# Bee_Hive_MainBoard.net
KiCad netlist of a schematic drawn in Altium Designer
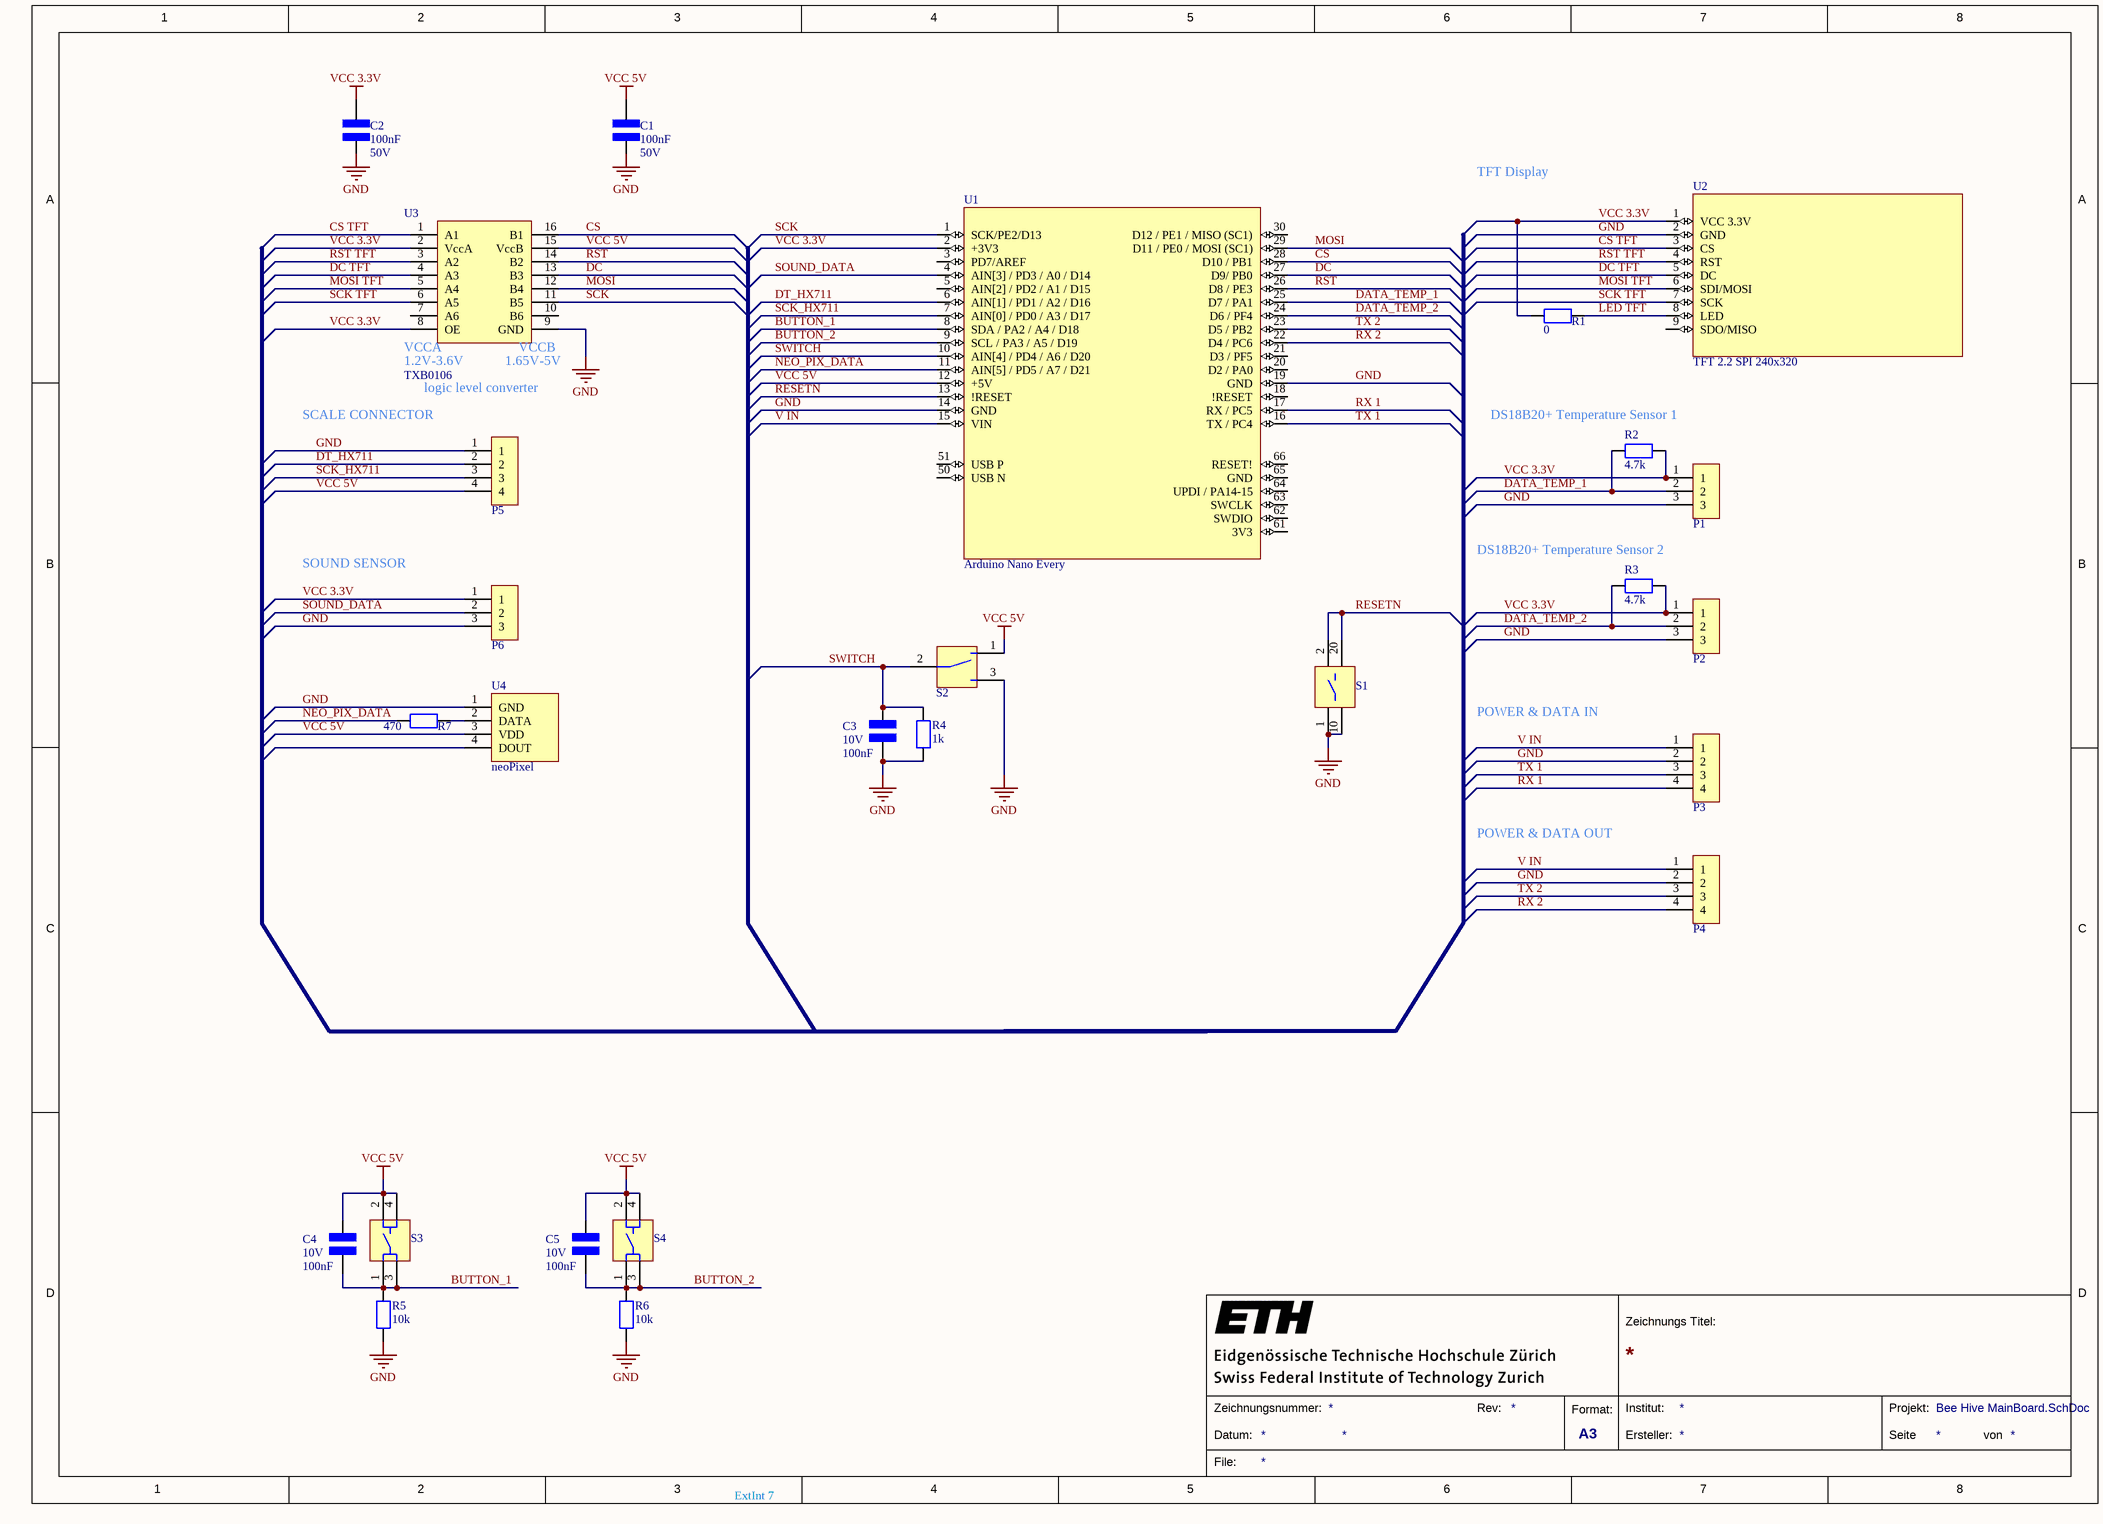
[diagram p0: Bee Hive MainBoard.SchDoc]

(export (version "E")
  (design (tool "Eeschema 10.0.6"))
  (components
    (comp (ref "C1")
      (value "100nF")
      (footprint "CAP 0603")
      (description "C CERAMIC SMD")
      (fields (field (name "UMAX") "50V") (field (name "Comment") "100nF 0603_1"))
      (libsource (lib "Library CAP") (part "100nF 0603_1"))
    )
    (comp (ref "C2")
      (value "100nF")
      (footprint "CAP 0603")
      (description "C CERAMIC SMD")
      (fields (field (name "UMAX") "50V") (field (name "Comment") "100nF 0603_1"))
      (libsource (lib "Library CAP") (part "100nF 0603_1"))
    )
    (comp (ref "C3")
      (value "100nF")
      (footprint "CAP 0603")
      (description "C CERAMIC SMD")
      (fields (field (name "UMAX") "10V") (field (name "Comment") "100nF 0603"))
      (libsource (lib "Library CAP") (part "100nF 0603"))
    )
    (comp (ref "C4")
      (value "100nF")
      (footprint "CAP 0603")
      (description "C CERAMIC SMD")
      (fields (field (name "UMAX") "10V") (field (name "Comment") "100nF 0603"))
      (libsource (lib "Library CAP") (part "100nF 0603"))
    )
    (comp (ref "C5")
      (value "100nF")
      (footprint "CAP 0603")
      (description "C CERAMIC SMD")
      (fields (field (name "UMAX") "10V") (field (name "Comment") "100nF 0603"))
      (libsource (lib "Library CAP") (part "100nF 0603"))
    )
    (comp (ref "P1")
      (value "3-Pin Right Angle Housing")
      (footprint "3PIN - RND 205-EK254-2.54-03P")
      (description "3-Pin")
      (libsource (lib "Library Scematic") (part "3-Pin Screw Terminal"))
    )
    (comp (ref "P2")
      (value "3-Pin Right Angle Housing")
      (footprint "3PIN - RND 205-EK254-2.54-03P")
      (description "3-Pin")
      (libsource (lib "Library Scematic") (part "3-Pin Screw Terminal"))
    )
    (comp (ref "P3")
      (value "4-Pin Right Angle Housing")
      (footprint "4PIN - RND 205-EK254-2.54-04P")
      (description "4-Pin")
      (libsource (lib "Library Scematic") (part "4-Pin Screw Terminal"))
    )
    (comp (ref "P4")
      (value "4-Pin Right Angle Housing")
      (footprint "4PIN - RND 205-EK254-2.54-04P")
      (description "4-Pin")
      (libsource (lib "Library Scematic") (part "4-Pin Screw Terminal"))
    )
    (comp (ref "P5")
      (value "4-Pin Right Angle Housing")
      (footprint "4PIN - RND 205-EK254-2.54-04P")
      (description "4-Pin")
      (libsource (lib "Library Scematic") (part "4-Pin Screw Terminal"))
    )
    (comp (ref "P6")
      (value "3-Pin Right Angle Housing")
      (footprint "3PIN - RND 205-EK254-2.54-03P")
      (description "3-Pin")
      (libsource (lib "Library Scematic") (part "3-Pin Screw Terminal"))
    )
    (comp (ref "R1")
      (value "0")
      (footprint "RES 0603 FOOTPRINT")
      (description "R SMD")
      (fields (field (name "Comment") "0 Ohm 0603"))
      (libsource (lib "Library RES") (part "0 Ohm 0603"))
    )
    (comp (ref "R2")
      (value "4.7k")
      (footprint "RES 0603 FOOTPRINT")
      (description "R SMD")
      (fields (field (name "Comment") "4.7k Ohm 0603"))
      (libsource (lib "Library RES") (part "4.7k Ohm 0603"))
    )
    (comp (ref "R3")
      (value "4.7k")
      (footprint "RES 0603 FOOTPRINT")
      (description "R SMD")
      (fields (field (name "Comment") "4.7k Ohm 0603"))
      (libsource (lib "Library RES") (part "4.7k Ohm 0603"))
    )
    (comp (ref "R4")
      (value "1k")
      (footprint "RES 0603 FOOTPRINT")
      (description "R SMD")
      (fields (field (name "Comment") "1k Ohm 0603"))
      (libsource (lib "Library RES") (part "1k Ohm 0603"))
    )
    (comp (ref "R5")
      (value "10k")
      (footprint "RES 0603 FOOTPRINT")
      (description "R SMD")
      (fields (field (name "Comment") "10k Ohm 0603"))
      (libsource (lib "Library RES") (part "10k Ohm 0603"))
    )
    (comp (ref "R6")
      (value "10k")
      (footprint "RES 0603 FOOTPRINT")
      (description "R SMD")
      (fields (field (name "Comment") "10k Ohm 0603"))
      (libsource (lib "Library RES") (part "10k Ohm 0603"))
    )
    (comp (ref "R7")
      (value "470")
      (footprint "RES 0603 FOOTPRINT")
      (description "R SMD")
      (fields (field (name "Comment") "470 Ohm 0603"))
      (libsource (lib "Library RES") (part "470 Ohm 0603"))
    )
    (comp (ref "S1")
      (value "Taster Print_SMD_2")
      (footprint "Taster Print - SMD - KMR241G LFS")
      (description "Taster")
      (libsource (lib "Library Scematic") (part "Taster Print_SMD_2"))
    )
    (comp (ref "S2")
      (value "Schiebeschalter 7A11-A1PCAE2")
      (footprint "schiebeschalter 7A11-A1PCAE2")
      (libsource (lib "Library Scematic") (part "Schiebeschalter 7A11-A1PCAE2"))
    )
    (comp (ref "S3")
      (value "Taster Print_SMD_3")
      (footprint "Taster Print RND 210-00212")
      (description "Taster")
      (libsource (lib "Library Scematic") (part "Taster Print_SMD_5"))
    )
    (comp (ref "S4")
      (value "Taster Print_SMD_3")
      (footprint "Taster Print RND 210-00212")
      (description "Taster")
      (libsource (lib "Library Scematic") (part "Taster Print_SMD_5"))
    )
    (comp (ref "U1")
      (value "Arduino Nano Every")
      (footprint "Arduino Nano Every")
      (description "https://store.arduino.cc/nano-every-pack")
      (libsource (lib "Library Scematic") (part "Arduino Nano Every"))
    )
    (comp (ref "U2")
      (value "TFT 2.2 SPI 240x320")
      (footprint "TFT 2.2 SPI 240x320")
      (libsource (lib "Library Scematic") (part "TFT 2.2 SPI 240x320"))
    )
    (comp (ref "U3")
      (value "TXB0106")
      (footprint "TSSOP-16L")
      (description "Level Converter TXB0106")
      (libsource (lib "Library Scematic") (part "TXB0106 Level Converter"))
    )
    (comp (ref "U4")
      (value "neoPixel")
      (footprint "neoPixel 5050 adafruit 1655")
      (description "neoPixel 5050 adafruit 1655")
      (libsource (lib "Library Scematic") (part "neoPixel 5050 adafruit 1655"))
    )
  )
  (nets
    (net (code "1") (name "/BUTTON_1") (class "Default")
      (node (ref "C4") (pin "2") (pinfunction "2_2") (pintype "passive"))
      (node (ref "R5") (pin "2") (pinfunction "2_2") (pintype "passive"))
      (node (ref "S3") (pin "1") (pinfunction "1_1") (pintype "passive"))
      (node (ref "S3") (pin "3") (pinfunction "3_3") (pintype "passive"))
      (node (ref "U1") (pin "8") (pinfunction "SDA_/_PA2_/_A4_/_D18_8") (pintype "bidirectional"))
    )
    (net (code "2") (name "/BUTTON_2") (class "Default")
      (node (ref "C5") (pin "2") (pinfunction "2_2") (pintype "passive"))
      (node (ref "R6") (pin "2") (pinfunction "2_2") (pintype "passive"))
      (node (ref "S4") (pin "1") (pinfunction "1_1") (pintype "passive"))
      (node (ref "S4") (pin "3") (pinfunction "3_3") (pintype "passive"))
      (node (ref "U1") (pin "9") (pinfunction "SCL_/_PA3_/_A5_/_D19_9") (pintype "bidirectional"))
    )
    (net (code "3") (name "/CS") (class "Default")
      (node (ref "U1") (pin "28") (pinfunction "D10_/_PB1_28") (pintype "bidirectional"))
      (node (ref "U3") (pin "16") (pinfunction "B1_16") (pintype "passive"))
    )
    (net (code "4") (name "/CS TFT") (class "Default")
      (node (ref "U2") (pin "3") (pinfunction "CS_3") (pintype "bidirectional"))
      (node (ref "U3") (pin "1") (pinfunction "A1_1") (pintype "power_in"))
    )
    (net (code "5") (name "/DATA_TEMP_1") (class "Default")
      (node (ref "P1") (pin "2") (pinfunction "2_2") (pintype "passive"))
      (node (ref "R2") (pin "2") (pinfunction "2_2") (pintype "passive"))
      (node (ref "U1") (pin "25") (pinfunction "D7_/_PA1_25") (pintype "bidirectional"))
    )
    (net (code "6") (name "/DATA_TEMP_2") (class "Default")
      (node (ref "P2") (pin "2") (pinfunction "2_2") (pintype "passive"))
      (node (ref "R3") (pin "2") (pinfunction "2_2") (pintype "passive"))
      (node (ref "U1") (pin "24") (pinfunction "D6_/_PF4_24") (pintype "bidirectional"))
    )
    (net (code "7") (name "/DC") (class "Default")
      (node (ref "U1") (pin "27") (pinfunction "D9/_PB0_27") (pintype "bidirectional"))
      (node (ref "U3") (pin "13") (pinfunction "B3_13") (pintype "passive"))
    )
    (net (code "8") (name "/DC TFT") (class "Default")
      (node (ref "U2") (pin "5") (pinfunction "DC_5") (pintype "bidirectional"))
      (node (ref "U3") (pin "4") (pinfunction "A3_4") (pintype "passive"))
    )
    (net (code "9") (name "/DT_HX711") (class "Default")
      (node (ref "P5") (pin "2") (pinfunction "2_2") (pintype "passive"))
      (node (ref "U1") (pin "6") (pinfunction "AIN[1]_/_PD1_/_A2_/_D16_6") (pintype "bidirectional"))
    )
    (net (code "10") (name "/LED TFT") (class "Default")
      (node (ref "R1") (pin "1") (pinfunction "1_1") (pintype "passive"))
      (node (ref "U2") (pin "8") (pinfunction "LED_8") (pintype "bidirectional"))
    )
    (net (code "11") (name "/MOSI") (class "Default")
      (node (ref "U1") (pin "29") (pinfunction "D11_/_PE0_/_MOSI_(SC1)_29") (pintype "bidirectional"))
      (node (ref "U3") (pin "12") (pinfunction "B4_12") (pintype "passive"))
    )
    (net (code "12") (name "/MOSI TFT") (class "Default")
      (node (ref "U2") (pin "6") (pinfunction "SDI/MOSI_6") (pintype "bidirectional"))
      (node (ref "U3") (pin "5") (pinfunction "A4_5") (pintype "passive"))
    )
    (net (code "13") (name "/NEO_PIX_DATA") (class "Default")
      (node (ref "R7") (pin "1") (pinfunction "1_1") (pintype "passive"))
      (node (ref "U1") (pin "11") (pinfunction "AIN[5]_/_PD5_/_A7_/_D21_11") (pintype "bidirectional"))
    )
    (net (code "14") (name "/RESETN") (class "Default")
      (node (ref "S1") (pin "2") (pinfunction "2_2") (pintype "passive"))
      (node (ref "S1") (pin "20") (pinfunction "20_20") (pintype "passive"))
      (node (ref "U1") (pin "13") (pinfunction "!RESET_13") (pintype "bidirectional"))
    )
    (net (code "15") (name "/RST") (class "Default")
      (node (ref "U1") (pin "26") (pinfunction "D8_/_PE3_26") (pintype "bidirectional"))
      (node (ref "U3") (pin "14") (pinfunction "B2_14") (pintype "passive"))
    )
    (net (code "16") (name "/RST TFT") (class "Default")
      (node (ref "U2") (pin "4") (pinfunction "RST_4") (pintype "bidirectional"))
      (node (ref "U3") (pin "3") (pinfunction "A2_3") (pintype "passive"))
    )
    (net (code "17") (name "/RX 1") (class "Default")
      (node (ref "P3") (pin "4") (pinfunction "4_4") (pintype "passive"))
      (node (ref "U1") (pin "17") (pinfunction "RX_/_PC5_17") (pintype "bidirectional"))
    )
    (net (code "18") (name "/RX 2") (class "Default")
      (node (ref "P4") (pin "4") (pinfunction "4_4") (pintype "passive"))
      (node (ref "U1") (pin "22") (pinfunction "D4_/_PC6_22") (pintype "bidirectional"))
    )
    (net (code "19") (name "/SCK") (class "Default")
      (node (ref "U1") (pin "1") (pinfunction "SCK/PE2/D13_1") (pintype "bidirectional"))
      (node (ref "U3") (pin "11") (pinfunction "B5_11") (pintype "passive"))
    )
    (net (code "20") (name "/SCK TFT") (class "Default")
      (node (ref "U2") (pin "7") (pinfunction "SCK_7") (pintype "bidirectional"))
      (node (ref "U3") (pin "6") (pinfunction "A5_6") (pintype "passive"))
    )
    (net (code "21") (name "/SCK_HX711") (class "Default")
      (node (ref "P5") (pin "3") (pinfunction "3_3") (pintype "passive"))
      (node (ref "U1") (pin "7") (pinfunction "AIN[0]_/_PD0_/_A3_/_D17_7") (pintype "bidirectional"))
    )
    (net (code "22") (name "/SOUND_DATA") (class "Default")
      (node (ref "P6") (pin "2") (pinfunction "2_2") (pintype "passive"))
      (node (ref "U1") (pin "4") (pinfunction "AIN[3]_/_PD3_/_A0_/_D14_4") (pintype "bidirectional"))
    )
    (net (code "23") (name "/SWITCH") (class "Default")
      (node (ref "C3") (pin "1") (pinfunction "1_1") (pintype "passive"))
      (node (ref "R4") (pin "2") (pinfunction "2_2") (pintype "passive"))
      (node (ref "S2") (pin "2") (pinfunction "2_2") (pintype "passive"))
      (node (ref "U1") (pin "10") (pinfunction "AIN[4]_/_PD4_/_A6_/_D20_10") (pintype "bidirectional"))
    )
    (net (code "24") (name "/TX 1") (class "Default")
      (node (ref "P3") (pin "3") (pinfunction "3_3") (pintype "passive"))
      (node (ref "U1") (pin "16") (pinfunction "TX_/_PC4_16") (pintype "bidirectional"))
    )
    (net (code "25") (name "/TX 2") (class "Default")
      (node (ref "P4") (pin "3") (pinfunction "3_3") (pintype "passive"))
      (node (ref "U1") (pin "23") (pinfunction "D5_/_PB2_23") (pintype "bidirectional"))
    )
    (net (code "26") (name "/V IN") (class "Default")
      (node (ref "P3") (pin "1") (pinfunction "1_1") (pintype "passive"))
      (node (ref "P4") (pin "1") (pinfunction "1_1") (pintype "passive"))
      (node (ref "U1") (pin "15") (pinfunction "VIN_15") (pintype "bidirectional"))
    )
    (net (code "27") (name "GND") (class "Default")
      (node (ref "C1") (pin "1") (pinfunction "1_1") (pintype "passive"))
      (node (ref "C2") (pin "1") (pinfunction "1_1") (pintype "passive"))
      (node (ref "C3") (pin "2") (pinfunction "2_2") (pintype "passive"))
      (node (ref "P1") (pin "3") (pinfunction "3_3") (pintype "passive"))
      (node (ref "P2") (pin "3") (pinfunction "3_3") (pintype "passive"))
      (node (ref "P3") (pin "2") (pinfunction "2_2") (pintype "passive"))
      (node (ref "P4") (pin "2") (pinfunction "2_2") (pintype "passive"))
      (node (ref "P5") (pin "1") (pinfunction "1_1") (pintype "passive"))
      (node (ref "P6") (pin "3") (pinfunction "3_3") (pintype "passive"))
      (node (ref "R4") (pin "1") (pinfunction "1_1") (pintype "passive"))
      (node (ref "R5") (pin "1") (pinfunction "1_1") (pintype "passive"))
      (node (ref "R6") (pin "1") (pinfunction "1_1") (pintype "passive"))
      (node (ref "S1") (pin "1") (pinfunction "1_1") (pintype "passive"))
      (node (ref "S1") (pin "10") (pinfunction "10_10") (pintype "passive"))
      (node (ref "S2") (pin "3") (pinfunction "3_3") (pintype "passive"))
      (node (ref "U1") (pin "14") (pinfunction "GND_14") (pintype "bidirectional"))
      (node (ref "U1") (pin "19") (pinfunction "GND_19") (pintype "bidirectional"))
      (node (ref "U2") (pin "2") (pinfunction "GND_2") (pintype "bidirectional"))
      (node (ref "U3") (pin "9") (pinfunction "GND_9") (pintype "passive"))
      (node (ref "U4") (pin "1") (pinfunction "GND_1") (pintype "passive"))
    )
    (net (code "28") (name "Net-(U4-DATA)") (class "Default")
      (node (ref "R7") (pin "2") (pinfunction "2_2") (pintype "passive"))
      (node (ref "U4") (pin "2") (pinfunction "DATA_2") (pintype "passive"))
    )
    (net (code "29") (name "VCC 3.3V") (class "Default")
      (node (ref "C2") (pin "2") (pinfunction "2_2") (pintype "passive"))
      (node (ref "P1") (pin "1") (pinfunction "1_1") (pintype "passive"))
      (node (ref "P2") (pin "1") (pinfunction "1_1") (pintype "passive"))
      (node (ref "P6") (pin "1") (pinfunction "1_1") (pintype "passive"))
      (node (ref "R1") (pin "2") (pinfunction "2_2") (pintype "passive"))
      (node (ref "R2") (pin "1") (pinfunction "1_1") (pintype "passive"))
      (node (ref "R3") (pin "1") (pinfunction "1_1") (pintype "passive"))
      (node (ref "U1") (pin "2") (pinfunction "+3V3_2") (pintype "bidirectional"))
      (node (ref "U2") (pin "1") (pinfunction "VCC_3.3V_1") (pintype "bidirectional"))
      (node (ref "U3") (pin "2") (pinfunction "VccA_2") (pintype "passive"))
      (node (ref "U3") (pin "8") (pinfunction "OE_8") (pintype "passive"))
    )
    (net (code "30") (name "VCC 5V") (class "Default")
      (node (ref "C1") (pin "2") (pinfunction "2_2") (pintype "passive"))
      (node (ref "C4") (pin "1") (pinfunction "1_1") (pintype "passive"))
      (node (ref "C5") (pin "1") (pinfunction "1_1") (pintype "passive"))
      (node (ref "P5") (pin "4") (pinfunction "4_4") (pintype "passive"))
      (node (ref "S2") (pin "1") (pinfunction "1_1") (pintype "passive"))
      (node (ref "S3") (pin "2") (pinfunction "2_2") (pintype "passive"))
      (node (ref "S3") (pin "4") (pinfunction "4_4") (pintype "passive"))
      (node (ref "S4") (pin "2") (pinfunction "2_2") (pintype "passive"))
      (node (ref "S4") (pin "4") (pinfunction "4_4") (pintype "passive"))
      (node (ref "U1") (pin "12") (pinfunction "+5V_12") (pintype "bidirectional"))
      (node (ref "U3") (pin "15") (pinfunction "VccB_15") (pintype "passive"))
      (node (ref "U4") (pin "3") (pinfunction "VDD_3") (pintype "passive"))
    )
    (net (code "31") (name "unconnected-(U1-!RESET-Pad18)") (class "Default")
      (node (ref "U1") (pin "18") (pinfunction "!RESET_18") (pintype "bidirectional"))
    )
    (net (code "32") (name "unconnected-(U1-3V3-Pad61)") (class "Default")
      (node (ref "U1") (pin "61") (pinfunction "3V3_61") (pintype "bidirectional"))
    )
    (net (code "33") (name "unconnected-(U1-AIN[2]_{slash}_PD2_{slash}_A1_{slash}_D15-Pad5)") (class "Default")
      (node (ref "U1") (pin "5") (pinfunction "AIN[2]_/_PD2_/_A1_/_D15_5") (pintype "bidirectional"))
    )
    (net (code "34") (name "unconnected-(U1-D2_{slash}_PA0-Pad20)") (class "Default")
      (node (ref "U1") (pin "20") (pinfunction "D2_/_PA0_20") (pintype "bidirectional"))
    )
    (net (code "35") (name "unconnected-(U1-D3_{slash}_PF5-Pad21)") (class "Default")
      (node (ref "U1") (pin "21") (pinfunction "D3_/_PF5_21") (pintype "bidirectional"))
    )
    (net (code "36") (name "unconnected-(U1-D12_{slash}_PE1_{slash}_MISO_(SC1)-Pad30)") (class "Default")
      (node (ref "U1") (pin "30") (pinfunction "D12_/_PE1_/_MISO_(SC1)_30") (pintype "bidirectional"))
    )
    (net (code "37") (name "unconnected-(U1-GND-Pad65)") (class "Default")
      (node (ref "U1") (pin "65") (pinfunction "GND_65") (pintype "bidirectional"))
    )
    (net (code "38") (name "unconnected-(U1-PD7{slash}AREF-Pad3)") (class "Default")
      (node (ref "U1") (pin "3") (pinfunction "PD7/AREF_3") (pintype "bidirectional"))
    )
    (net (code "39") (name "unconnected-(U1-RESET!-Pad66)") (class "Default")
      (node (ref "U1") (pin "66") (pinfunction "RESET!_66") (pintype "bidirectional"))
    )
    (net (code "40") (name "unconnected-(U1-SWCLK-Pad63)") (class "Default")
      (node (ref "U1") (pin "63") (pinfunction "SWCLK_63") (pintype "bidirectional"))
    )
    (net (code "41") (name "unconnected-(U1-SWDIO-Pad62)") (class "Default")
      (node (ref "U1") (pin "62") (pinfunction "SWDIO_62") (pintype "bidirectional"))
    )
    (net (code "42") (name "unconnected-(U1-UPDI_{slash}_PA14-15-Pad64)") (class "Default")
      (node (ref "U1") (pin "64") (pinfunction "UPDI_/_PA14-15_64") (pintype "bidirectional"))
    )
    (net (code "43") (name "unconnected-(U1-USB_N-Pad50)") (class "Default")
      (node (ref "U1") (pin "50") (pinfunction "USB_N_50") (pintype "bidirectional"))
    )
    (net (code "44") (name "unconnected-(U1-USB_P-Pad51)") (class "Default")
      (node (ref "U1") (pin "51") (pinfunction "USB_P_51") (pintype "bidirectional"))
    )
    (net (code "45") (name "unconnected-(U2-SDO{slash}MISO-Pad9)") (class "Default")
      (node (ref "U2") (pin "9") (pinfunction "SDO/MISO_9") (pintype "bidirectional"))
    )
    (net (code "46") (name "unconnected-(U3-A6-Pad7)") (class "Default")
      (node (ref "U3") (pin "7") (pinfunction "A6_7") (pintype "passive"))
    )
    (net (code "47") (name "unconnected-(U3-B6-Pad10)") (class "Default")
      (node (ref "U3") (pin "10") (pinfunction "B6_10") (pintype "passive"))
    )
    (net (code "48") (name "unconnected-(U4-DOUT-Pad4)") (class "Default")
      (node (ref "U4") (pin "4") (pinfunction "DOUT_4") (pintype "passive"))
    )
  )
)
